# Conectors.net
KiCad netlist of a schematic drawn in Altium Designer
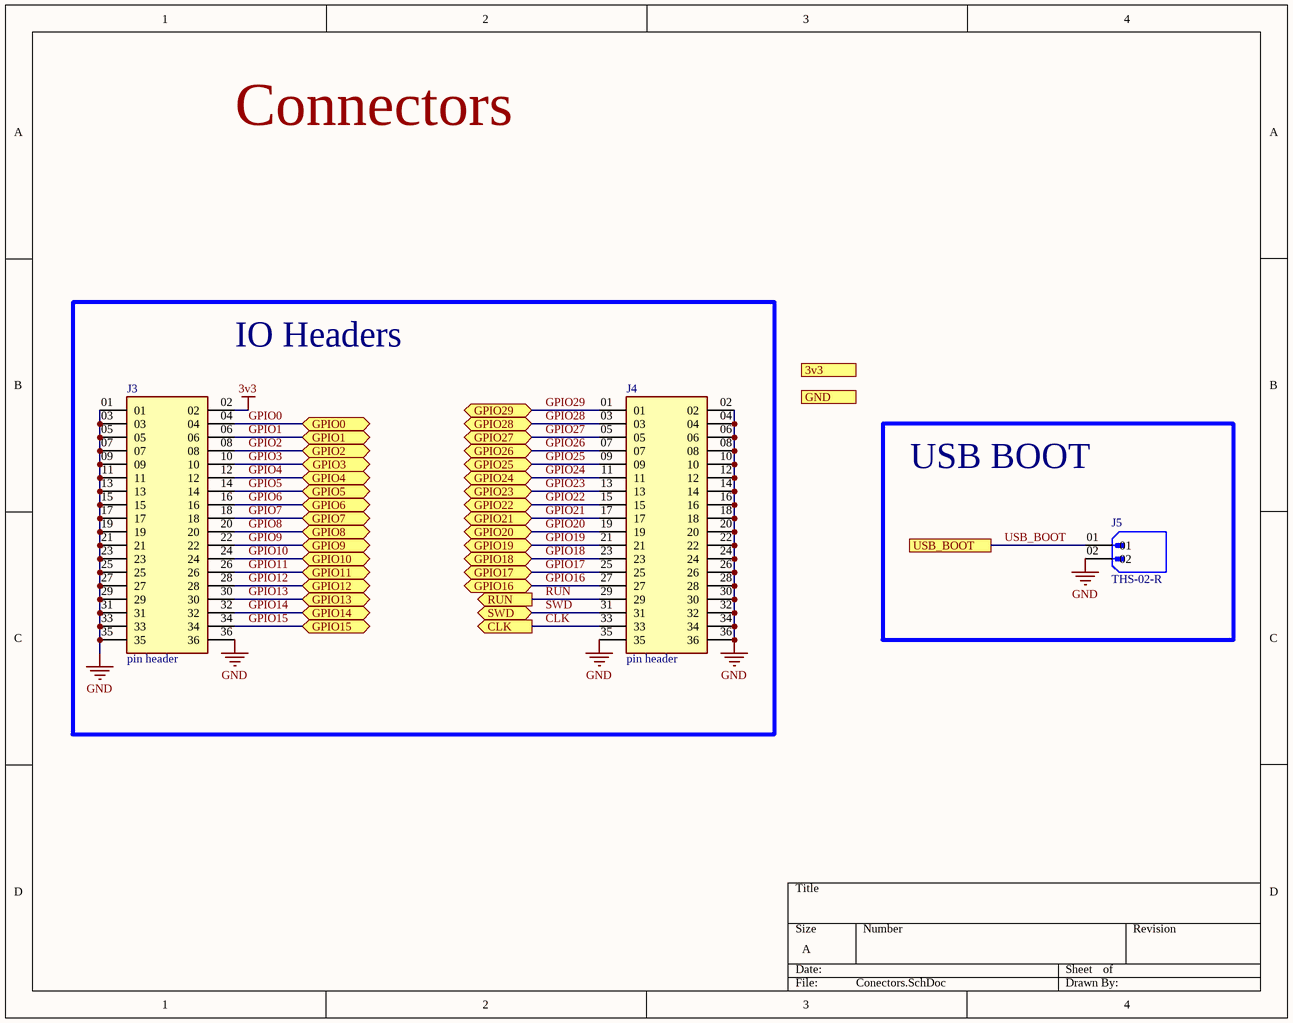
[diagram p0: Conectors.SchDoc]

(export (version "E")
  (design (tool "Eeschema 10.0.6"))
  (components
    (comp (ref "J3")
      (value "pin header")
      (footprint "MTSW-118-07-T-D-150")
      (description "2x18 male pin header")
      (fields (field (name "MP") "MTSW-118-07-T-D-150"))
      (libsource (lib "RP2040intLib") (part "MTSW-118-07-T-D-150"))
    )
    (comp (ref "J4")
      (value "pin header")
      (footprint "MTSW-118-07-T-D-150")
      (description "2x18 male pin header")
      (fields (field (name "MP") "MTSW-118-07-T-D-150"))
      (libsource (lib "RP2040intLib") (part "MTSW-118-07-T-D-150"))
    )
    (comp (ref "J5")
      (value "THS-02-R")
      (footprint "THS-02-R")
      (description "2x1 male pin header")
      (libsource (lib "RP2040intLib") (part "THS-02-R"))
    )
  )
  (nets
    (net (code "1") (name "/CLK") (class "Default")
      (node (ref "J4") (pin "33") (pinfunction "33_33") (pintype "passive"))
    )
    (net (code "2") (name "/GPIO0") (class "Default")
      (node (ref "J3") (pin "04") (pinfunction "04_04") (pintype "passive"))
    )
    (net (code "3") (name "/GPIO1") (class "Default")
      (node (ref "J3") (pin "06") (pinfunction "06_06") (pintype "passive"))
    )
    (net (code "4") (name "/GPIO2") (class "Default")
      (node (ref "J3") (pin "08") (pinfunction "08_08") (pintype "passive"))
    )
    (net (code "5") (name "/GPIO3") (class "Default")
      (node (ref "J3") (pin "10") (pinfunction "10_10") (pintype "passive"))
    )
    (net (code "6") (name "/GPIO4") (class "Default")
      (node (ref "J3") (pin "12") (pinfunction "12_12") (pintype "passive"))
    )
    (net (code "7") (name "/GPIO5") (class "Default")
      (node (ref "J3") (pin "14") (pinfunction "14_14") (pintype "passive"))
    )
    (net (code "8") (name "/GPIO6") (class "Default")
      (node (ref "J3") (pin "16") (pinfunction "16_16") (pintype "passive"))
    )
    (net (code "9") (name "/GPIO7") (class "Default")
      (node (ref "J3") (pin "18") (pinfunction "18_18") (pintype "passive"))
    )
    (net (code "10") (name "/GPIO8") (class "Default")
      (node (ref "J3") (pin "20") (pinfunction "20_20") (pintype "passive"))
    )
    (net (code "11") (name "/GPIO9") (class "Default")
      (node (ref "J3") (pin "22") (pinfunction "22_22") (pintype "passive"))
    )
    (net (code "12") (name "/GPIO10") (class "Default")
      (node (ref "J3") (pin "24") (pinfunction "24_24") (pintype "passive"))
    )
    (net (code "13") (name "/GPIO11") (class "Default")
      (node (ref "J3") (pin "26") (pinfunction "26_26") (pintype "passive"))
    )
    (net (code "14") (name "/GPIO12") (class "Default")
      (node (ref "J3") (pin "28") (pinfunction "28_28") (pintype "passive"))
    )
    (net (code "15") (name "/GPIO13") (class "Default")
      (node (ref "J3") (pin "30") (pinfunction "30_30") (pintype "passive"))
    )
    (net (code "16") (name "/GPIO14") (class "Default")
      (node (ref "J3") (pin "32") (pinfunction "32_32") (pintype "passive"))
    )
    (net (code "17") (name "/GPIO15") (class "Default")
      (node (ref "J3") (pin "34") (pinfunction "34_34") (pintype "passive"))
    )
    (net (code "18") (name "/GPIO16") (class "Default")
      (node (ref "J4") (pin "27") (pinfunction "27_27") (pintype "passive"))
    )
    (net (code "19") (name "/GPIO17") (class "Default")
      (node (ref "J4") (pin "25") (pinfunction "25_25") (pintype "passive"))
    )
    (net (code "20") (name "/GPIO18") (class "Default")
      (node (ref "J4") (pin "23") (pinfunction "23_23") (pintype "passive"))
    )
    (net (code "21") (name "/GPIO19") (class "Default")
      (node (ref "J4") (pin "21") (pinfunction "21_21") (pintype "passive"))
    )
    (net (code "22") (name "/GPIO20") (class "Default")
      (node (ref "J4") (pin "19") (pinfunction "19_19") (pintype "passive"))
    )
    (net (code "23") (name "/GPIO21") (class "Default")
      (node (ref "J4") (pin "17") (pinfunction "17_17") (pintype "passive"))
    )
    (net (code "24") (name "/GPIO22") (class "Default")
      (node (ref "J4") (pin "15") (pinfunction "15_15") (pintype "passive"))
    )
    (net (code "25") (name "/GPIO23") (class "Default")
      (node (ref "J4") (pin "13") (pinfunction "13_13") (pintype "passive"))
    )
    (net (code "26") (name "/GPIO24") (class "Default")
      (node (ref "J4") (pin "11") (pinfunction "11_11") (pintype "passive"))
    )
    (net (code "27") (name "/GPIO25") (class "Default")
      (node (ref "J4") (pin "09") (pinfunction "09_09") (pintype "passive"))
    )
    (net (code "28") (name "/GPIO26") (class "Default")
      (node (ref "J4") (pin "07") (pinfunction "07_07") (pintype "passive"))
    )
    (net (code "29") (name "/GPIO27") (class "Default")
      (node (ref "J4") (pin "05") (pinfunction "05_05") (pintype "passive"))
    )
    (net (code "30") (name "/GPIO28") (class "Default")
      (node (ref "J4") (pin "03") (pinfunction "03_03") (pintype "passive"))
    )
    (net (code "31") (name "/GPIO29") (class "Default")
      (node (ref "J4") (pin "01") (pinfunction "01_01") (pintype "passive"))
    )
    (net (code "32") (name "/RUN") (class "Default")
      (node (ref "J4") (pin "29") (pinfunction "29_29") (pintype "passive"))
    )
    (net (code "33") (name "/SWD") (class "Default")
      (node (ref "J4") (pin "31") (pinfunction "31_31") (pintype "passive"))
    )
    (net (code "34") (name "/USB_BOOT") (class "Default")
      (node (ref "J5") (pin "01") (pinfunction "01_01") (pintype "passive"))
    )
    (net (code "35") (name "3v3") (class "Default")
      (node (ref "J3") (pin "02") (pinfunction "02_02") (pintype "passive"))
    )
    (net (code "36") (name "GND") (class "Default")
      (node (ref "J3") (pin "01") (pinfunction "01_01") (pintype "passive"))
      (node (ref "J3") (pin "03") (pinfunction "03_03") (pintype "passive"))
      (node (ref "J3") (pin "05") (pinfunction "05_05") (pintype "passive"))
      (node (ref "J3") (pin "07") (pinfunction "07_07") (pintype "passive"))
      (node (ref "J3") (pin "09") (pinfunction "09_09") (pintype "passive"))
      (node (ref "J3") (pin "11") (pinfunction "11_11") (pintype "passive"))
      (node (ref "J3") (pin "13") (pinfunction "13_13") (pintype "passive"))
      (node (ref "J3") (pin "15") (pinfunction "15_15") (pintype "passive"))
      (node (ref "J3") (pin "17") (pinfunction "17_17") (pintype "passive"))
      (node (ref "J3") (pin "19") (pinfunction "19_19") (pintype "passive"))
      (node (ref "J3") (pin "21") (pinfunction "21_21") (pintype "passive"))
      (node (ref "J3") (pin "23") (pinfunction "23_23") (pintype "passive"))
      (node (ref "J3") (pin "25") (pinfunction "25_25") (pintype "passive"))
      (node (ref "J3") (pin "27") (pinfunction "27_27") (pintype "passive"))
      (node (ref "J3") (pin "29") (pinfunction "29_29") (pintype "passive"))
      (node (ref "J3") (pin "31") (pinfunction "31_31") (pintype "passive"))
      (node (ref "J3") (pin "33") (pinfunction "33_33") (pintype "passive"))
      (node (ref "J3") (pin "35") (pinfunction "35_35") (pintype "passive"))
      (node (ref "J3") (pin "36") (pinfunction "36_36") (pintype "passive"))
      (node (ref "J4") (pin "02") (pinfunction "02_02") (pintype "passive"))
      (node (ref "J4") (pin "04") (pinfunction "04_04") (pintype "passive"))
      (node (ref "J4") (pin "06") (pinfunction "06_06") (pintype "passive"))
      (node (ref "J4") (pin "08") (pinfunction "08_08") (pintype "passive"))
      (node (ref "J4") (pin "10") (pinfunction "10_10") (pintype "passive"))
      (node (ref "J4") (pin "12") (pinfunction "12_12") (pintype "passive"))
      (node (ref "J4") (pin "14") (pinfunction "14_14") (pintype "passive"))
      (node (ref "J4") (pin "16") (pinfunction "16_16") (pintype "passive"))
      (node (ref "J4") (pin "18") (pinfunction "18_18") (pintype "passive"))
      (node (ref "J4") (pin "20") (pinfunction "20_20") (pintype "passive"))
      (node (ref "J4") (pin "22") (pinfunction "22_22") (pintype "passive"))
      (node (ref "J4") (pin "24") (pinfunction "24_24") (pintype "passive"))
      (node (ref "J4") (pin "26") (pinfunction "26_26") (pintype "passive"))
      (node (ref "J4") (pin "28") (pinfunction "28_28") (pintype "passive"))
      (node (ref "J4") (pin "30") (pinfunction "30_30") (pintype "passive"))
      (node (ref "J4") (pin "32") (pinfunction "32_32") (pintype "passive"))
      (node (ref "J4") (pin "34") (pinfunction "34_34") (pintype "passive"))
      (node (ref "J4") (pin "35") (pinfunction "35_35") (pintype "passive"))
      (node (ref "J4") (pin "36") (pinfunction "36_36") (pintype "passive"))
      (node (ref "J5") (pin "02") (pinfunction "02_02") (pintype "passive"))
    )
  )
)
